# board_wifi_v1.net
KiCad netlist of a schematic drawn in EAGLE
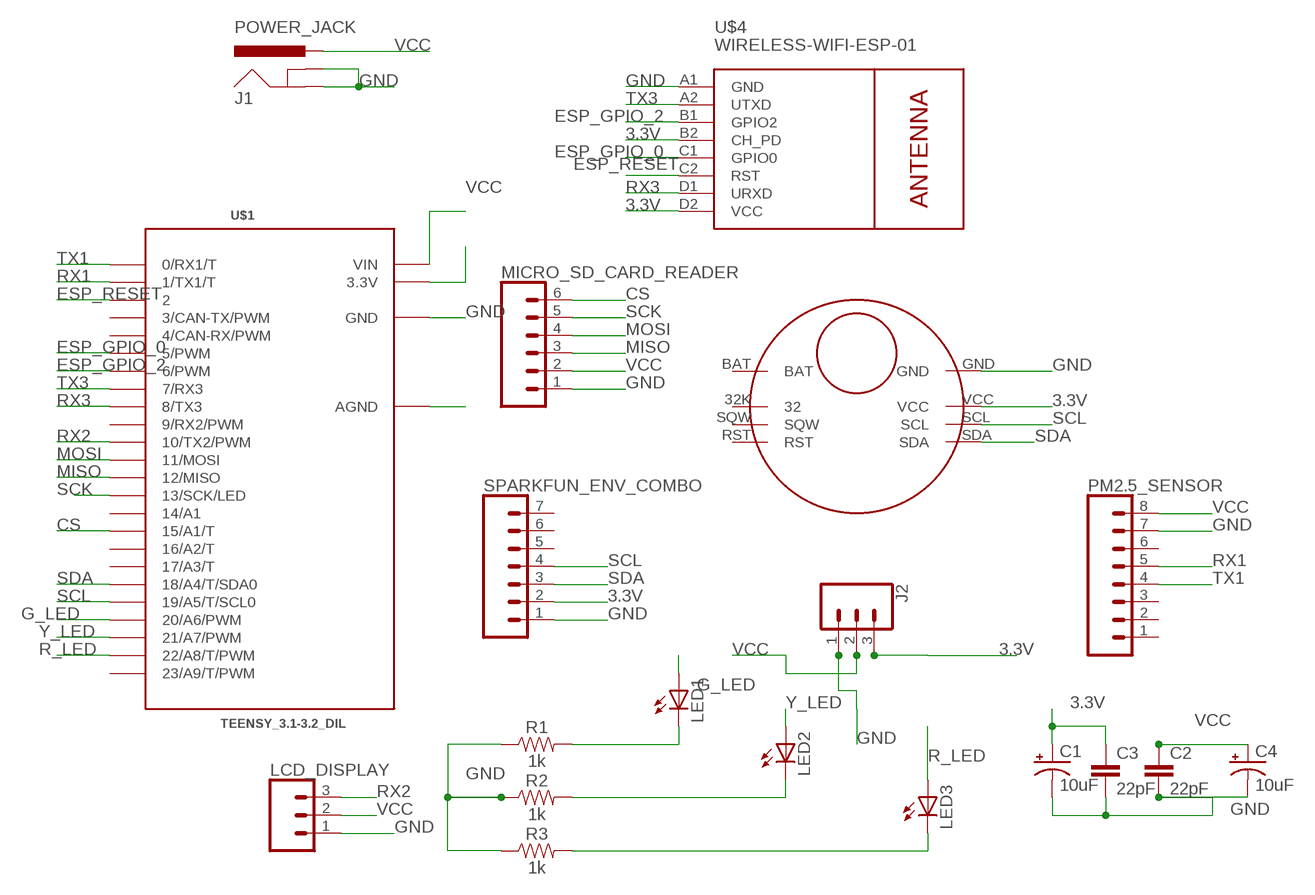
[diagram p0: schematic, sheet 1]

(export (version "E")
  (design (tool "Eeschema 10.0.6"))
  (components
    (comp (ref "C1")
      (value "10uF")
      (footprint "eagle-import:CPOL-RADIAL-2.5MM-5MM")
      (libsource (lib "eagle-import") (part "10UF-POLAR-RADIAL-2.5MM-25V-20%"))
    )
    (comp (ref "C2")
      (value "22pF")
      (footprint "eagle-import:CAP-PTH-2.54")
      (libsource (lib "eagle-import") (part "22PF-PTH-2.54MM-200V-5%"))
    )
    (comp (ref "C3")
      (value "22pF")
      (footprint "eagle-import:CAP-PTH-2.54")
      (libsource (lib "eagle-import") (part "22PF-PTH-2.54MM-200V-5%"))
    )
    (comp (ref "C4")
      (value "10uF")
      (footprint "eagle-import:CPOL-RADIAL-2.5MM-5MM")
      (libsource (lib "eagle-import") (part "10UF-POLAR-RADIAL-2.5MM-25V-20%"))
    )
    (comp (ref "J1")
      (value "POWER_JACK")
      (footprint "eagle-import:POWER_JACK_PTH")
      (libsource (lib "eagle-import") (part "POWER_JACK"))
    )
    (comp (ref "J2")
      (value "CONN_03LONGPADS")
      (footprint "eagle-import:1X03_LONGPADS")
      (libsource (lib "eagle-import") (part "CONN_03LONGPADS"))
    )
    (comp (ref "LCD_DISPLAY")
      (value "CONN_031X03_NO_SILK")
      (footprint "eagle-import:1X03_NO_SILK")
      (libsource (lib "eagle-import") (part "CONN_031X03_NO_SILK"))
    )
    (comp (ref "LED1")
      (value "LED3MM")
      (footprint "eagle-import:LED3MM")
      (libsource (lib "eagle-import") (part "LED3MM"))
    )
    (comp (ref "LED2")
      (value "LED3MM")
      (footprint "eagle-import:LED3MM")
      (libsource (lib "eagle-import") (part "LED3MM"))
    )
    (comp (ref "LED3")
      (value "LED3MM")
      (footprint "eagle-import:LED3MM")
      (libsource (lib "eagle-import") (part "LED3MM"))
    )
    (comp (ref "MICRO_SD_CARD_READER")
      (value "CONN_06LONGPADS")
      (footprint "eagle-import:1X06_LONGPADS")
      (libsource (lib "eagle-import") (part "CONN_06LONGPADS"))
    )
    (comp (ref "PM2.5_SENSOR")
      (value "CONN_08NO_SILK_FEMALE_PTH")
      (footprint "eagle-import:1X08_NO_SILK")
      (libsource (lib "eagle-import") (part "CONN_08NO_SILK_FEMALE_PTH"))
    )
    (comp (ref "R1")
      (value "1k")
      (footprint "eagle-import:AXIAL-0.3")
      (libsource (lib "eagle-import") (part "1KOHM-HORIZ-1/4W-5%"))
    )
    (comp (ref "R2")
      (value "1k")
      (footprint "eagle-import:AXIAL-0.3")
      (libsource (lib "eagle-import") (part "1KOHM-HORIZ-1/4W-5%"))
    )
    (comp (ref "R3")
      (value "1k")
      (footprint "eagle-import:AXIAL-0.3")
      (libsource (lib "eagle-import") (part "1KOHM-HORIZ-1/4W-5%"))
    )
    (comp (ref "SPARKFUN_ENV_COMBO")
      (value "CONN_07NO_SILK")
      (footprint "eagle-import:1X07_NO_SILK")
      (libsource (lib "eagle-import") (part "CONN_07NO_SILK"))
    )
    (comp (ref "U$1")
      (value "TEENSY_3.1-3.2_DIL")
      (footprint "eagle-import:TEENSY_3.0-3.2&LC_DIL")
      (libsource (lib "eagle-import") (part "TEENSY_3.1-3.2_DIL"))
    )
    (comp (ref "U$2")
      (value "RTCCLOCK")
      (footprint "eagle-import:RTCCLOCK")
      (libsource (lib "eagle-import") (part "RTCCLOCK"))
    )
    (comp (ref "U$4")
      (value "WIRELESS-WIFI-ESP-01")
      (footprint "eagle-import:WIRELESS-WIFI-ESP-01")
      (libsource (lib "eagle-import") (part "WIRELESS-WIFI-ESP-01"))
    )
  )
  (nets
    (net (code "1") (name "/3.3V") (class "Default")
      (node (ref "C1") (pin "1") (pinfunction "+_1") (pintype "passive"))
      (node (ref "C3") (pin "1") (pinfunction "1_1") (pintype "passive"))
      (node (ref "J2") (pin "3") (pinfunction "3_3") (pintype "passive"))
      (node (ref "SPARKFUN_ENV_COMBO") (pin "2") (pinfunction "2_2") (pintype "passive"))
      (node (ref "U$2") (pin "VCC") (pinfunction "VCC_VCC") (pintype "bidirectional"))
      (node (ref "U$4") (pin "B2") (pinfunction "CH_PD_B2") (pintype "bidirectional"))
      (node (ref "U$4") (pin "D2") (pinfunction "VCC_D2") (pintype "power_in"))
    )
    (net (code "2") (name "/CS") (class "Default")
      (node (ref "MICRO_SD_CARD_READER") (pin "6") (pinfunction "6_6") (pintype "passive"))
      (node (ref "U$1") (pin "15/A1") (pinfunction "15/A1/T_15/A1") (pintype "bidirectional"))
    )
    (net (code "3") (name "/ESP_GPIO_0") (class "Default")
      (node (ref "U$1") (pin "5") (pinfunction "5/PWM_5") (pintype "bidirectional"))
      (node (ref "U$4") (pin "C1") (pinfunction "GPIO0_C1") (pintype "bidirectional"))
    )
    (net (code "4") (name "/ESP_GPIO_2") (class "Default")
      (node (ref "U$1") (pin "6") (pinfunction "6/PWM_6") (pintype "bidirectional"))
      (node (ref "U$4") (pin "B1") (pinfunction "GPIO2_B1") (pintype "bidirectional"))
    )
    (net (code "5") (name "/ESP_RESET") (class "Default")
      (node (ref "U$1") (pin "2") (pinfunction "2_2") (pintype "bidirectional"))
      (node (ref "U$4") (pin "C2") (pinfunction "RST_C2") (pintype "bidirectional"))
    )
    (net (code "6") (name "/GND") (class "Default")
      (node (ref "C1") (pin "2") (pinfunction "-_2") (pintype "passive"))
      (node (ref "C2") (pin "2") (pinfunction "2_2") (pintype "passive"))
      (node (ref "C3") (pin "2") (pinfunction "2_2") (pintype "passive"))
      (node (ref "C4") (pin "2") (pinfunction "-_2") (pintype "passive"))
      (node (ref "J1") (pin "GND") (pinfunction "GND_GND") (pintype "bidirectional"))
      (node (ref "J1") (pin "GNDBREAK") (pinfunction "GNDBREAK_GNDBREAK") (pintype "bidirectional"))
      (node (ref "J2") (pin "1") (pinfunction "1_1") (pintype "passive"))
      (node (ref "LCD_DISPLAY") (pin "1") (pinfunction "1_1") (pintype "passive"))
      (node (ref "MICRO_SD_CARD_READER") (pin "1") (pinfunction "1_1") (pintype "passive"))
      (node (ref "PM2.5_SENSOR") (pin "7") (pinfunction "7_7") (pintype "passive"))
      (node (ref "R1") (pin "P$1") (pinfunction "1_P$1") (pintype "passive"))
      (node (ref "R2") (pin "P$1") (pinfunction "1_P$1") (pintype "passive"))
      (node (ref "R3") (pin "P$1") (pinfunction "1_P$1") (pintype "passive"))
      (node (ref "SPARKFUN_ENV_COMBO") (pin "1") (pinfunction "1_1") (pintype "passive"))
      (node (ref "U$1") (pin "GND") (pinfunction "GND_GND") (pintype "power_in"))
      (node (ref "U$2") (pin "GND") (pinfunction "GND_GND") (pintype "bidirectional"))
      (node (ref "U$4") (pin "A1") (pinfunction "GND_A1") (pintype "power_in"))
    )
    (net (code "7") (name "/G_LED") (class "Default")
      (node (ref "LED1") (pin "A") (pinfunction "A_A") (pintype "passive"))
      (node (ref "U$1") (pin "20/A6") (pinfunction "20/A6/PWM_20/A6") (pintype "bidirectional"))
    )
    (net (code "8") (name "/MISO") (class "Default")
      (node (ref "MICRO_SD_CARD_READER") (pin "3") (pinfunction "3_3") (pintype "passive"))
      (node (ref "U$1") (pin "12") (pinfunction "12/MISO_12") (pintype "bidirectional"))
    )
    (net (code "9") (name "/MOSI") (class "Default")
      (node (ref "MICRO_SD_CARD_READER") (pin "4") (pinfunction "4_4") (pintype "passive"))
      (node (ref "U$1") (pin "11") (pinfunction "11/MOSI_11") (pintype "bidirectional"))
    )
    (net (code "10") (name "/RX1") (class "Default")
      (node (ref "PM2.5_SENSOR") (pin "5") (pinfunction "5_5") (pintype "passive"))
      (node (ref "U$1") (pin "1") (pinfunction "1/TX1/T_1") (pintype "bidirectional"))
    )
    (net (code "11") (name "/RX2") (class "Default")
      (node (ref "LCD_DISPLAY") (pin "3") (pinfunction "3_3") (pintype "passive"))
      (node (ref "U$1") (pin "10") (pinfunction "10/TX2/PWM_10") (pintype "bidirectional"))
    )
    (net (code "12") (name "/RX3") (class "Default")
      (node (ref "U$1") (pin "8") (pinfunction "8/TX3_8") (pintype "bidirectional"))
      (node (ref "U$4") (pin "D1") (pinfunction "URXD_D1") (pintype "bidirectional"))
    )
    (net (code "13") (name "/R_LED") (class "Default")
      (node (ref "LED3") (pin "A") (pinfunction "A_A") (pintype "passive"))
      (node (ref "U$1") (pin "22/A8") (pinfunction "22/A8/T/PWM_22/A8") (pintype "bidirectional"))
    )
    (net (code "14") (name "/SCK") (class "Default")
      (node (ref "MICRO_SD_CARD_READER") (pin "5") (pinfunction "5_5") (pintype "passive"))
      (node (ref "U$1") (pin "13") (pinfunction "13/SCK/LED_13") (pintype "bidirectional"))
    )
    (net (code "15") (name "/SCL") (class "Default")
      (node (ref "SPARKFUN_ENV_COMBO") (pin "4") (pinfunction "4_4") (pintype "passive"))
      (node (ref "U$1") (pin "19/A5") (pinfunction "19/A5/T/SCL0_19/A5") (pintype "bidirectional"))
      (node (ref "U$2") (pin "SCL") (pinfunction "SCL_SCL") (pintype "bidirectional"))
    )
    (net (code "16") (name "/SDA") (class "Default")
      (node (ref "SPARKFUN_ENV_COMBO") (pin "3") (pinfunction "3_3") (pintype "passive"))
      (node (ref "U$1") (pin "18/A4") (pinfunction "18/A4/T/SDA0_18/A4") (pintype "bidirectional"))
      (node (ref "U$2") (pin "SDA") (pinfunction "SDA_SDA") (pintype "bidirectional"))
    )
    (net (code "17") (name "/TX1") (class "Default")
      (node (ref "PM2.5_SENSOR") (pin "4") (pinfunction "4_4") (pintype "passive"))
      (node (ref "U$1") (pin "0") (pinfunction "0/RX1/T_0") (pintype "bidirectional"))
    )
    (net (code "18") (name "/TX3") (class "Default")
      (node (ref "U$1") (pin "7") (pinfunction "7/RX3_7") (pintype "bidirectional"))
      (node (ref "U$4") (pin "A2") (pinfunction "UTXD_A2") (pintype "bidirectional"))
    )
    (net (code "19") (name "/VCC") (class "Default")
      (node (ref "C2") (pin "1") (pinfunction "1_1") (pintype "passive"))
      (node (ref "C4") (pin "1") (pinfunction "+_1") (pintype "passive"))
      (node (ref "J1") (pin "PWR") (pinfunction "PWR_PWR") (pintype "bidirectional"))
      (node (ref "J2") (pin "2") (pinfunction "2_2") (pintype "passive"))
      (node (ref "LCD_DISPLAY") (pin "2") (pinfunction "2_2") (pintype "passive"))
      (node (ref "MICRO_SD_CARD_READER") (pin "2") (pinfunction "2_2") (pintype "passive"))
      (node (ref "PM2.5_SENSOR") (pin "8") (pinfunction "8_8") (pintype "passive"))
      (node (ref "U$1") (pin "VIN") (pinfunction "VIN_VIN") (pintype "power_in"))
    )
    (net (code "20") (name "/Y_LED") (class "Default")
      (node (ref "LED2") (pin "A") (pinfunction "A_A") (pintype "passive"))
      (node (ref "U$1") (pin "21/A7") (pinfunction "21/A7/PWM_21/A7") (pintype "bidirectional"))
    )
    (net (code "21") (name "Net-(LED1-C)") (class "Default")
      (node (ref "LED1") (pin "K") (pinfunction "C_K") (pintype "passive"))
      (node (ref "R1") (pin "P$2") (pinfunction "2_P$2") (pintype "passive"))
    )
    (net (code "22") (name "Net-(LED2-C)") (class "Default")
      (node (ref "LED2") (pin "K") (pinfunction "C_K") (pintype "passive"))
      (node (ref "R2") (pin "P$2") (pinfunction "2_P$2") (pintype "passive"))
    )
    (net (code "23") (name "Net-(LED3-C)") (class "Default")
      (node (ref "LED3") (pin "K") (pinfunction "C_K") (pintype "passive"))
      (node (ref "R3") (pin "P$2") (pinfunction "2_P$2") (pintype "passive"))
    )
    (net (code "24") (name "unconnected-(PM2.5_SENSOR-Pad1)") (class "Default")
      (node (ref "PM2.5_SENSOR") (pin "1") (pinfunction "1_1") (pintype "passive"))
    )
    (net (code "25") (name "unconnected-(PM2.5_SENSOR-Pad2)") (class "Default")
      (node (ref "PM2.5_SENSOR") (pin "2") (pinfunction "2_2") (pintype "passive"))
    )
    (net (code "26") (name "unconnected-(PM2.5_SENSOR-Pad3)") (class "Default")
      (node (ref "PM2.5_SENSOR") (pin "3") (pinfunction "3_3") (pintype "passive"))
    )
    (net (code "27") (name "unconnected-(PM2.5_SENSOR-Pad6)") (class "Default")
      (node (ref "PM2.5_SENSOR") (pin "6") (pinfunction "6_6") (pintype "passive"))
    )
    (net (code "28") (name "unconnected-(SPARKFUN_ENV_COMBO-Pad5)") (class "Default")
      (node (ref "SPARKFUN_ENV_COMBO") (pin "5") (pinfunction "5_5") (pintype "passive"))
    )
    (net (code "29") (name "unconnected-(SPARKFUN_ENV_COMBO-Pad6)") (class "Default")
      (node (ref "SPARKFUN_ENV_COMBO") (pin "6") (pinfunction "6_6") (pintype "passive"))
    )
    (net (code "30") (name "unconnected-(SPARKFUN_ENV_COMBO-Pad7)") (class "Default")
      (node (ref "SPARKFUN_ENV_COMBO") (pin "7") (pinfunction "7_7") (pintype "passive"))
    )
    (net (code "31") (name "unconnected-(U$1-3{slash}CAN-TX{slash}PWM-Pad3)") (class "Default")
      (node (ref "U$1") (pin "3") (pinfunction "3/CAN-TX/PWM_3") (pintype "bidirectional"))
    )
    (net (code "32") (name "unconnected-(U$1-4{slash}CAN-RX{slash}PWM-Pad4)") (class "Default")
      (node (ref "U$1") (pin "4") (pinfunction "4/CAN-RX/PWM_4") (pintype "bidirectional"))
    )
    (net (code "33") (name "unconnected-(U$1-9{slash}RX2{slash}PWM-Pad9)") (class "Default")
      (node (ref "U$1") (pin "9") (pinfunction "9/RX2/PWM_9") (pintype "bidirectional"))
    )
    (net (code "34") (name "unconnected-(U$1-14{slash}A1-Pad14{slash}A0)") (class "Default")
      (node (ref "U$1") (pin "14/A0") (pinfunction "14/A1_14/A0") (pintype "bidirectional"))
    )
    (net (code "35") (name "unconnected-(U$1-16{slash}A2{slash}T-Pad16{slash}A2)") (class "Default")
      (node (ref "U$1") (pin "16/A2") (pinfunction "16/A2/T_16/A2") (pintype "bidirectional"))
    )
    (net (code "36") (name "unconnected-(U$1-17{slash}A3{slash}T-Pad17{slash}A3)") (class "Default")
      (node (ref "U$1") (pin "17/A3") (pinfunction "17/A3/T_17/A3") (pintype "bidirectional"))
    )
    (net (code "37") (name "unconnected-(U$1-23{slash}A9{slash}T{slash}PWM-Pad23{slash}A9)") (class "Default")
      (node (ref "U$1") (pin "23/A9") (pinfunction "23/A9/T/PWM_23/A9") (pintype "bidirectional"))
    )
    (net (code "38") (name "unconnected-(U$1-Pad3.3V)") (class "Default")
      (node (ref "U$1") (pin "3.3V") (pinfunction "3.3V_3.3V") (pintype "power_in"))
    )
    (net (code "39") (name "unconnected-(U$1-PadAGND)") (class "Default")
      (node (ref "U$1") (pin "AGND") (pinfunction "AGND_AGND") (pintype "power_in"))
    )
    (net (code "40") (name "unconnected-(U$2-32-Pad32K)") (class "Default")
      (node (ref "U$2") (pin "32K") (pinfunction "32_32K") (pintype "bidirectional"))
    )
    (net (code "41") (name "unconnected-(U$2-PadBAT)") (class "Default")
      (node (ref "U$2") (pin "BAT") (pinfunction "BAT_BAT") (pintype "bidirectional"))
    )
    (net (code "42") (name "unconnected-(U$2-PadRST)") (class "Default")
      (node (ref "U$2") (pin "RST") (pinfunction "RST_RST") (pintype "bidirectional"))
    )
    (net (code "43") (name "unconnected-(U$2-PadSQW)") (class "Default")
      (node (ref "U$2") (pin "SQW") (pinfunction "SQW_SQW") (pintype "bidirectional"))
    )
  )
)
